# NRF24-mini-SHIM.net
KiCad netlist of a schematic drawn in EAGLE
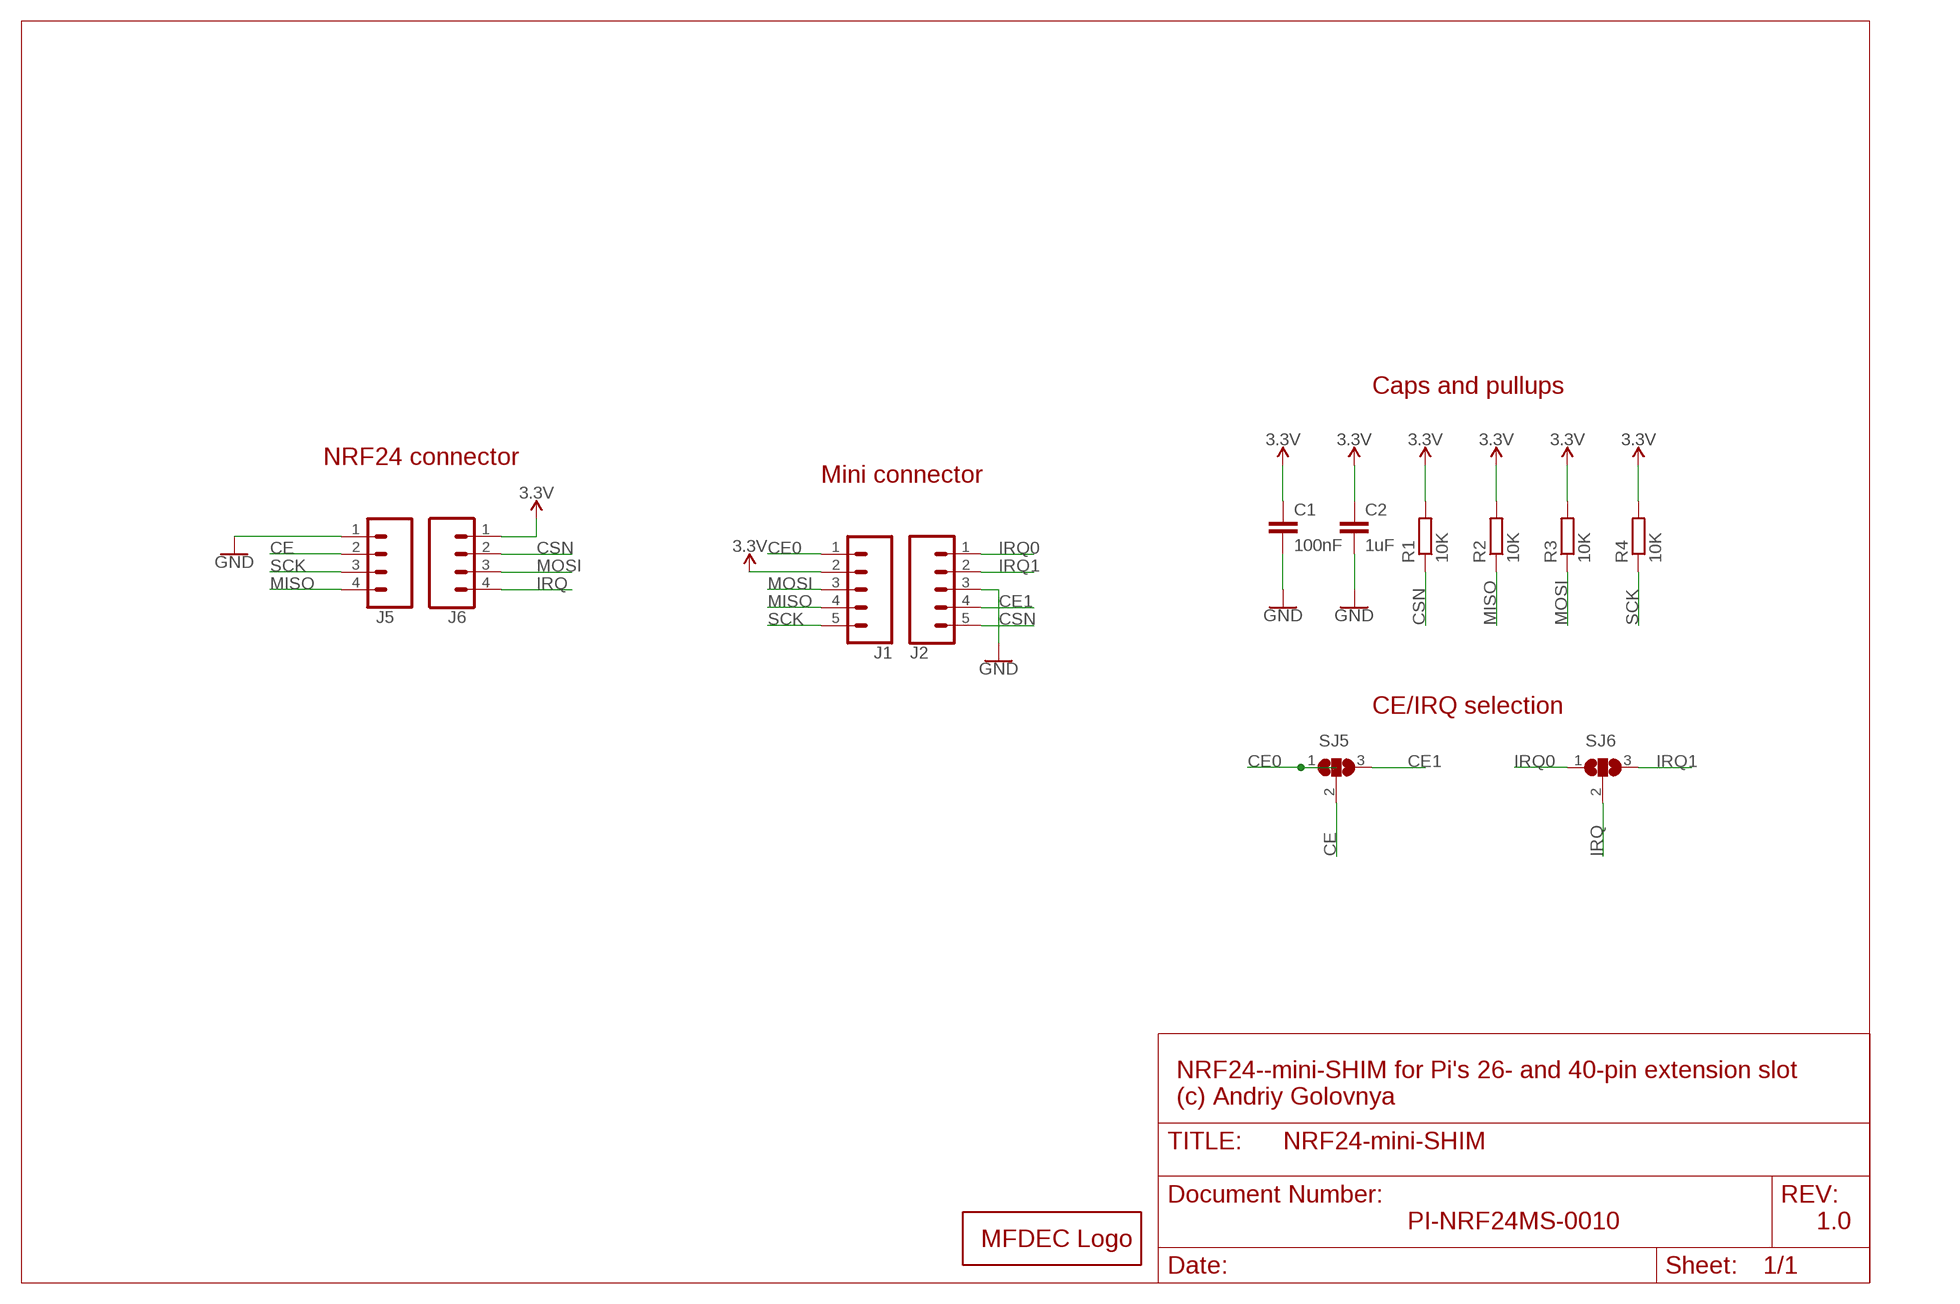
[diagram p0: schematic, sheet 1]

(export (version "E")
  (design (tool "Eeschema 10.0.6"))
  (components
    (comp (ref "C1")
      (value "100nF")
      (footprint "eagle-import:C0402")
      (libsource (lib "eagle-import") (part "C-EUC0402"))
    )
    (comp (ref "C2")
      (value "1uF")
      (footprint "eagle-import:C0603")
      (libsource (lib "eagle-import") (part "C-EUC0603"))
    )
    (comp (ref "J1")
      (value "CONN_05LOCK")
      (footprint "eagle-import:1X05_LOCK")
      (libsource (lib "eagle-import") (part "CONN_05LOCK"))
    )
    (comp (ref "J2")
      (value "CONN_05LOCK")
      (footprint "eagle-import:1X05_LOCK")
      (libsource (lib "eagle-import") (part "CONN_05LOCK"))
    )
    (comp (ref "J5")
      (value "CONN_04LOCK")
      (footprint "eagle-import:1X04_LOCK")
      (libsource (lib "eagle-import") (part "CONN_04LOCK"))
    )
    (comp (ref "J6")
      (value "CONN_04LOCK")
      (footprint "eagle-import:1X04_LOCK")
      (libsource (lib "eagle-import") (part "CONN_04LOCK"))
    )
    (comp (ref "LOGO1")
      (value "MFDECLOGO_L_10MM")
      (footprint "eagle-import:MFDEC_L_10MM")
      (libsource (lib "eagle-import") (part "MFDECLOGO_L_10MM"))
    )
    (comp (ref "R1")
      (value "10K")
      (footprint "eagle-import:R0402")
      (libsource (lib "eagle-import") (part "R-EU_R0402"))
    )
    (comp (ref "R2")
      (value "10K")
      (footprint "eagle-import:R0402")
      (libsource (lib "eagle-import") (part "R-EU_R0402"))
    )
    (comp (ref "R3")
      (value "10K")
      (footprint "eagle-import:R0402")
      (libsource (lib "eagle-import") (part "R-EU_R0402"))
    )
    (comp (ref "R4")
      (value "10K")
      (footprint "eagle-import:R0402")
      (libsource (lib "eagle-import") (part "R-EU_R0402"))
    )
    (comp (ref "SJ5")
      (value "SJ2")
      (footprint "eagle-import:SJ_2")
      (libsource (lib "eagle-import") (part "SJ2"))
    )
    (comp (ref "SJ6")
      (value "SJ2")
      (footprint "eagle-import:SJ_2")
      (libsource (lib "eagle-import") (part "SJ2"))
    )
  )
  (nets
    (net (code "1") (name "/CE") (class "Default")
      (node (ref "J5") (pin "2") (pinfunction "2_2") (pintype "passive"))
      (node (ref "SJ5") (pin "2") (pinfunction "2_2") (pintype "passive"))
    )
    (net (code "2") (name "/CE0") (class "Default")
      (node (ref "J1") (pin "1") (pinfunction "1_1") (pintype "passive"))
      (node (ref "SJ5") (pin "1") (pinfunction "1_1") (pintype "passive"))
    )
    (net (code "3") (name "/CE1") (class "Default")
      (node (ref "J2") (pin "4") (pinfunction "4_4") (pintype "passive"))
      (node (ref "SJ5") (pin "3") (pinfunction "3_3") (pintype "passive"))
    )
    (net (code "4") (name "/CSN") (class "Default")
      (node (ref "J2") (pin "5") (pinfunction "5_5") (pintype "passive"))
      (node (ref "J6") (pin "2") (pinfunction "2_2") (pintype "passive"))
      (node (ref "R1") (pin "1") (pinfunction "1_1") (pintype "passive"))
    )
    (net (code "5") (name "/IRQ") (class "Default")
      (node (ref "J6") (pin "4") (pinfunction "4_4") (pintype "passive"))
      (node (ref "SJ6") (pin "2") (pinfunction "2_2") (pintype "passive"))
    )
    (net (code "6") (name "/IRQ0") (class "Default")
      (node (ref "J2") (pin "1") (pinfunction "1_1") (pintype "passive"))
      (node (ref "SJ6") (pin "1") (pinfunction "1_1") (pintype "passive"))
    )
    (net (code "7") (name "/IRQ1") (class "Default")
      (node (ref "J2") (pin "2") (pinfunction "2_2") (pintype "passive"))
      (node (ref "SJ6") (pin "3") (pinfunction "3_3") (pintype "passive"))
    )
    (net (code "8") (name "/MISO") (class "Default")
      (node (ref "J1") (pin "4") (pinfunction "4_4") (pintype "passive"))
      (node (ref "J5") (pin "4") (pinfunction "4_4") (pintype "passive"))
      (node (ref "R2") (pin "1") (pinfunction "1_1") (pintype "passive"))
    )
    (net (code "9") (name "/MOSI") (class "Default")
      (node (ref "J1") (pin "3") (pinfunction "3_3") (pintype "passive"))
      (node (ref "J6") (pin "3") (pinfunction "3_3") (pintype "passive"))
      (node (ref "R3") (pin "1") (pinfunction "1_1") (pintype "passive"))
    )
    (net (code "10") (name "/SCK") (class "Default")
      (node (ref "J1") (pin "5") (pinfunction "5_5") (pintype "passive"))
      (node (ref "J5") (pin "3") (pinfunction "3_3") (pintype "passive"))
      (node (ref "R4") (pin "1") (pinfunction "1_1") (pintype "passive"))
    )
    (net (code "11") (name "3.3V") (class "Default")
      (node (ref "C1") (pin "1") (pinfunction "1_1") (pintype "passive"))
      (node (ref "C2") (pin "1") (pinfunction "1_1") (pintype "passive"))
      (node (ref "J1") (pin "2") (pinfunction "2_2") (pintype "passive"))
      (node (ref "J6") (pin "1") (pinfunction "1_1") (pintype "passive"))
      (node (ref "R1") (pin "2") (pinfunction "2_2") (pintype "passive"))
      (node (ref "R2") (pin "2") (pinfunction "2_2") (pintype "passive"))
      (node (ref "R3") (pin "2") (pinfunction "2_2") (pintype "passive"))
      (node (ref "R4") (pin "2") (pinfunction "2_2") (pintype "passive"))
    )
    (net (code "12") (name "GND") (class "Default")
      (node (ref "C1") (pin "2") (pinfunction "2_2") (pintype "passive"))
      (node (ref "C2") (pin "2") (pinfunction "2_2") (pintype "passive"))
      (node (ref "J2") (pin "3") (pinfunction "3_3") (pintype "passive"))
      (node (ref "J5") (pin "1") (pinfunction "1_1") (pintype "passive"))
    )
  )
)
